# GSMGPSMC60_2.net
KiCad netlist of a schematic drawn in Altium Designer
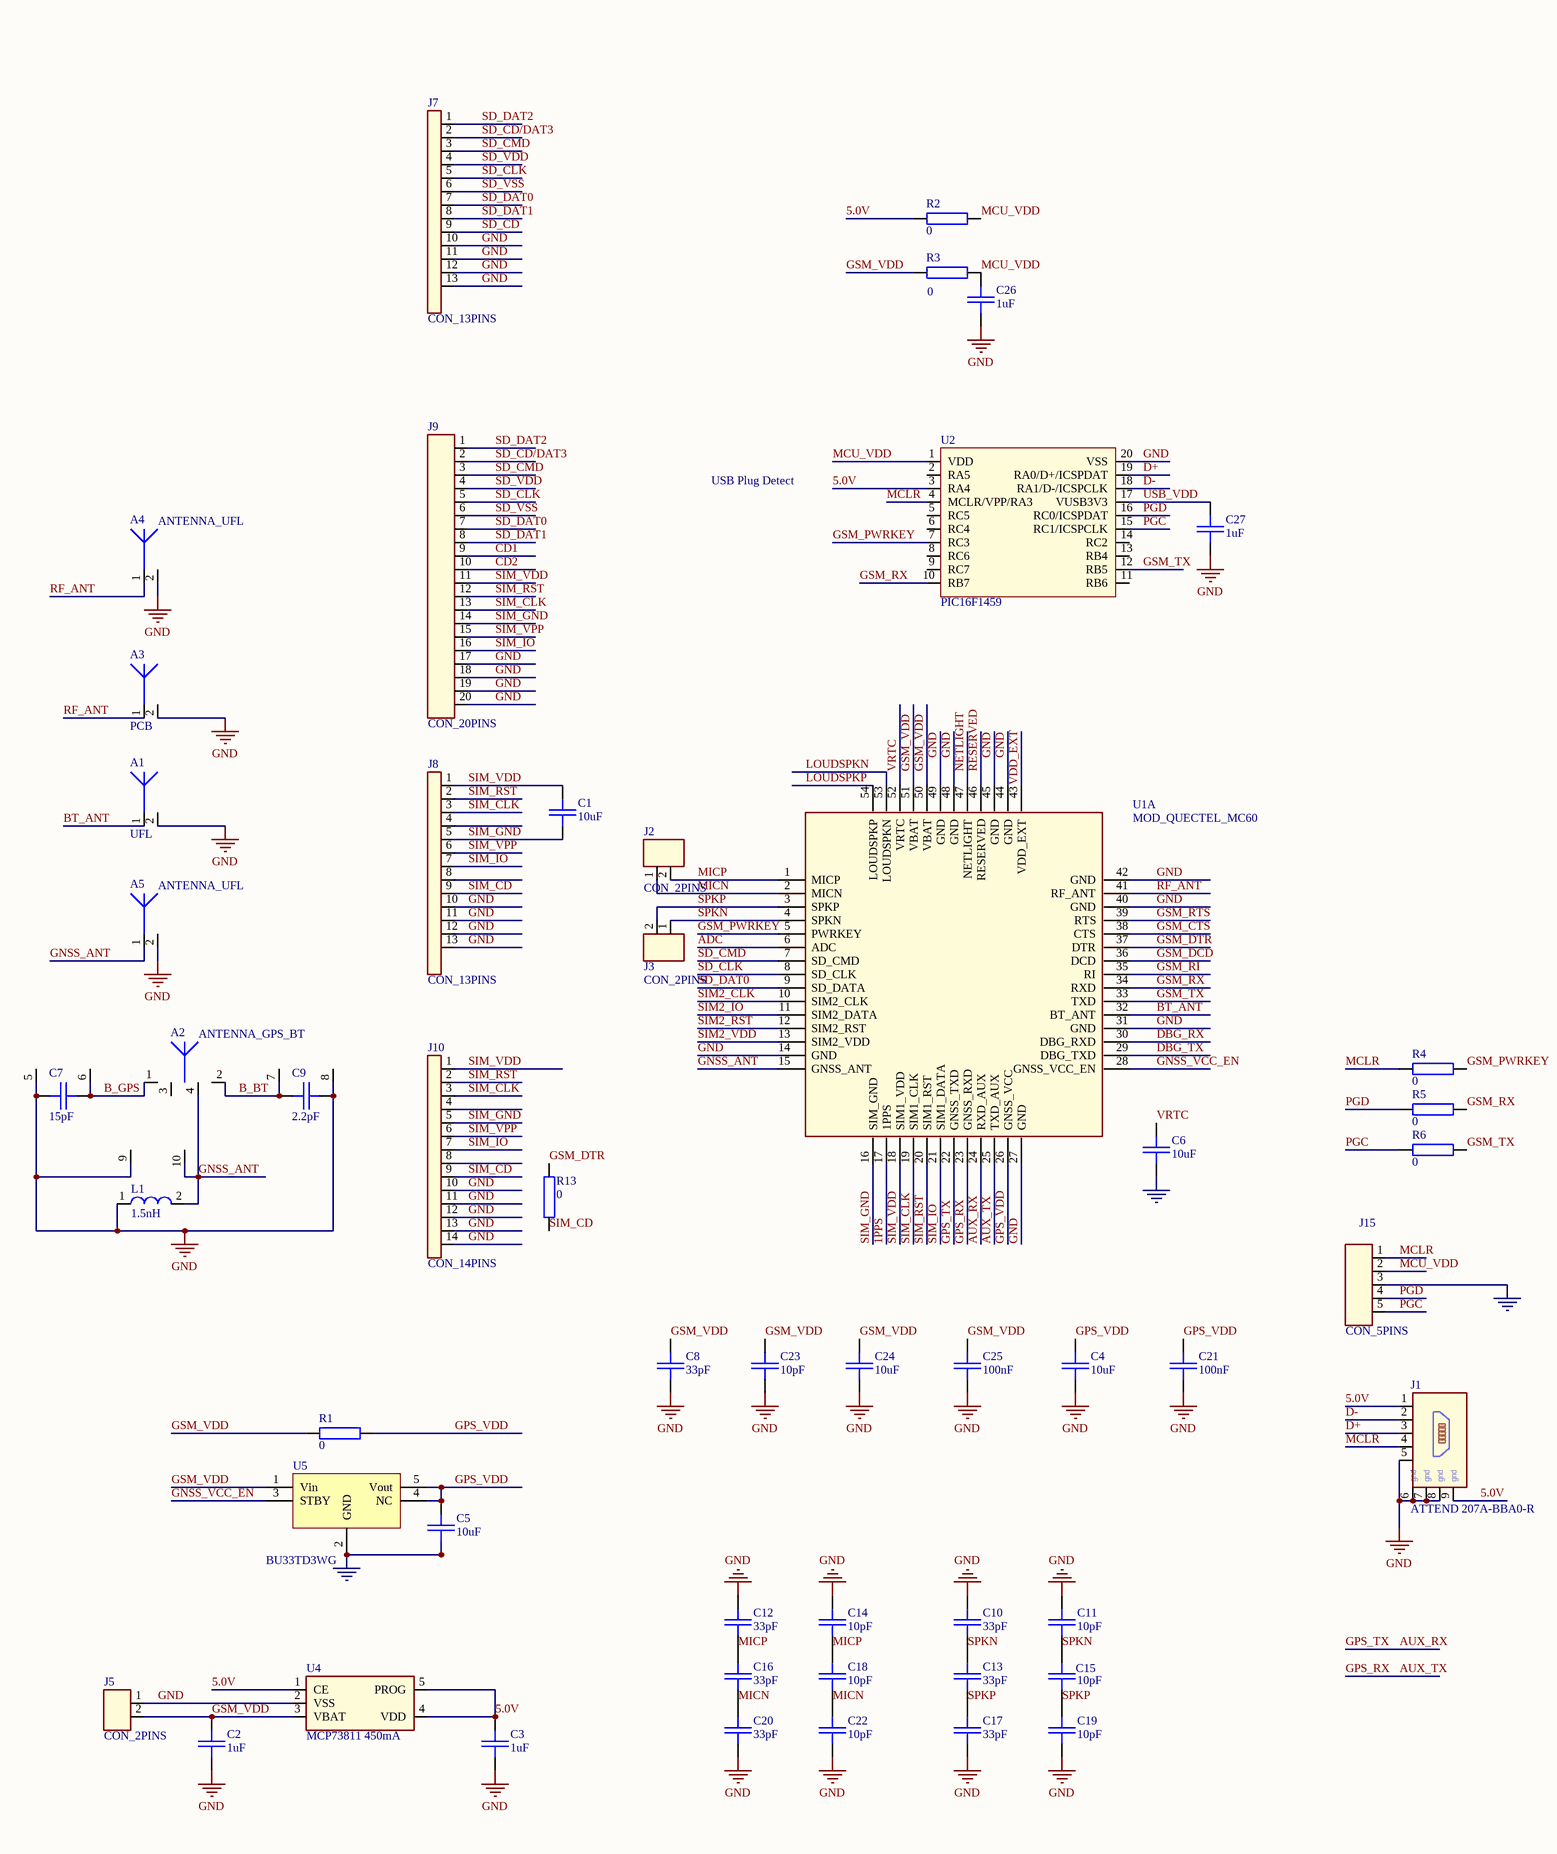
[diagram p0: GSMGPSMC60_2.SchDoc, left]
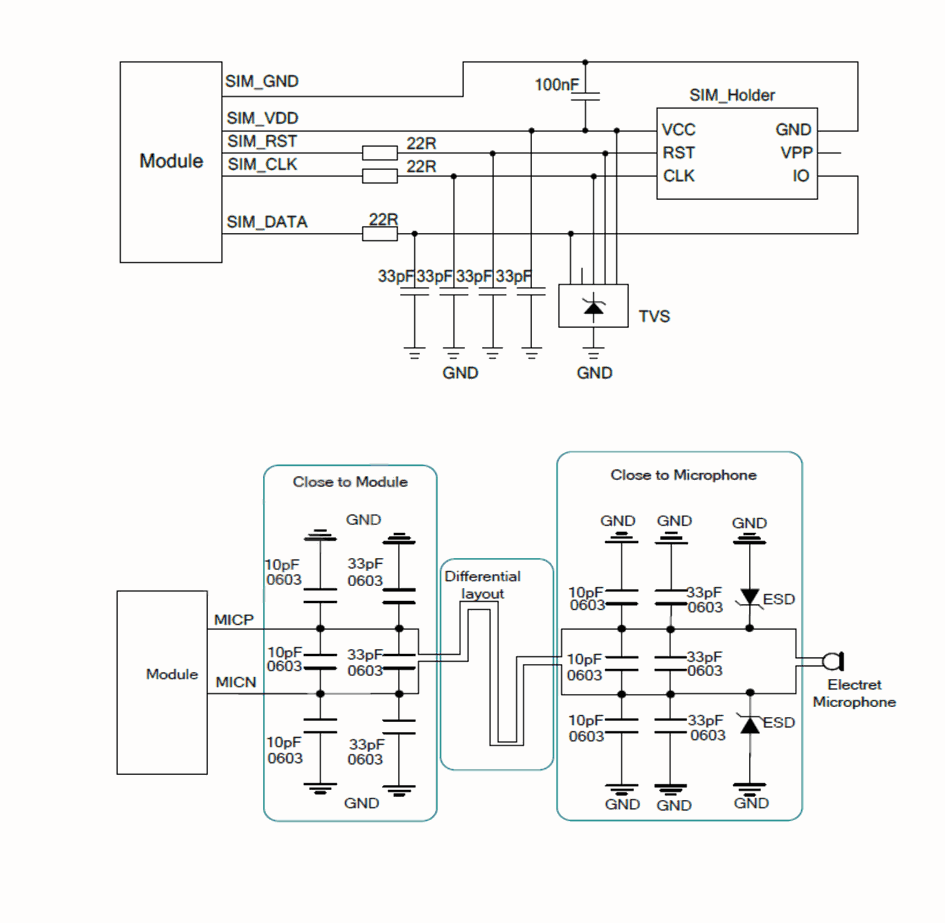
[diagram p1: GSMGPSMC60_2.SchDoc, right]

(export (version "E")
  (design (tool "Eeschema 10.0.6"))
  (components
    (comp (ref "A1")
      (value "UFL")
      (footprint "SMD_CON_ANTENNA_UFL")
      (libsource (lib "DLV") (part "ANTENNA_2"))
    )
    (comp (ref "A2")
      (value "ANTENNA_GPS_BT")
      (footprint "SMD_CHIP_ANTENNA_GPS_BT - FLIP")
      (libsource (lib "DLV") (part "ANTENNA_GPS_BT"))
    )
    (comp (ref "A3")
      (value "PCB")
      (footprint "SMD_CON_ANTENNA_GSM_PCB")
      (libsource (lib "DLV") (part "ANTENNA_2"))
    )
    (comp (ref "A4")
      (value "ANTENNA_UFL")
      (footprint "SMD_CON_ANTENNA_UFL")
      (libsource (lib "DLV") (part "ANTENNA_2"))
    )
    (comp (ref "A5")
      (value "ANTENNA_UFL")
      (footprint "SMD_CON_ANTENNA_UFL")
      (libsource (lib "DLV") (part "ANTENNA_2"))
    )
    (comp (ref "C1") (value "10uF") (footprint "SMD_0402_CAPC1005X90N") (libsource (lib "DLV") (part "C")))
    (comp (ref "C2") (value "1uF") (footprint "SMD_0402_CAPC1005X90N") (libsource (lib "DLV") (part "C")))
    (comp (ref "C3") (value "1uF") (footprint "SMD_0402_CAPC1005X90N") (libsource (lib "DLV") (part "C")))
    (comp (ref "C4") (value "10uF") (footprint "SMD_0402_CAPC1005X90N") (libsource (lib "DLV") (part "C")))
    (comp (ref "C5") (value "10uF") (footprint "SMD_0402_CAPC1005X90N") (libsource (lib "DLV") (part "C")))
    (comp (ref "C6") (value "10uF") (footprint "SMD_0402_CAPC1005X90N") (libsource (lib "DLV") (part "C")))
    (comp (ref "C7")
      (value "15pF")
      (footprint "SMD_0402_CAPC1005X90N - ANTENNA")
      (libsource (lib "DLV") (part "C"))
    )
    (comp (ref "C8") (value "33pF") (footprint "SMD_0402_CAPC1005X90N") (libsource (lib "DLV") (part "C")))
    (comp (ref "C9")
      (value "2.2pF")
      (footprint "SMD_0201_CAPC0603X33N - ANTENNA")
      (libsource (lib "DLV") (part "C"))
    )
    (comp (ref "C10") (value "33pF") (footprint "SMD_0402_CAPC1005X90N") (libsource (lib "DLV") (part "C")))
    (comp (ref "C11") (value "10pF") (footprint "SMD_0402_CAPC1005X90N") (libsource (lib "DLV") (part "C")))
    (comp (ref "C12") (value "33pF") (footprint "SMD_0402_CAPC1005X90N") (libsource (lib "DLV") (part "C")))
    (comp (ref "C13") (value "33pF") (footprint "SMD_0402_CAPC1005X90N") (libsource (lib "DLV") (part "C")))
    (comp (ref "C14") (value "10pF") (footprint "SMD_0402_CAPC1005X90N") (libsource (lib "DLV") (part "C")))
    (comp (ref "C15") (value "10pF") (footprint "SMD_0402_CAPC1005X90N") (libsource (lib "DLV") (part "C")))
    (comp (ref "C16") (value "33pF") (footprint "SMD_0402_CAPC1005X90N") (libsource (lib "DLV") (part "C")))
    (comp (ref "C17") (value "33pF") (footprint "SMD_0402_CAPC1005X90N") (libsource (lib "DLV") (part "C")))
    (comp (ref "C18") (value "10pF") (footprint "SMD_0402_CAPC1005X90N") (libsource (lib "DLV") (part "C")))
    (comp (ref "C19") (value "10pF") (footprint "SMD_0402_CAPC1005X90N") (libsource (lib "DLV") (part "C")))
    (comp (ref "C20") (value "33pF") (footprint "SMD_0402_CAPC1005X90N") (libsource (lib "DLV") (part "C")))
    (comp (ref "C21") (value "100nF") (footprint "SMD_0402_CAPC1005X90N") (libsource (lib "DLV") (part "C")))
    (comp (ref "C22") (value "10pF") (footprint "SMD_0402_CAPC1005X90N") (libsource (lib "DLV") (part "C")))
    (comp (ref "C23") (value "10pF") (footprint "SMD_0402_CAPC1005X90N") (libsource (lib "DLV") (part "C")))
    (comp (ref "C24") (value "10uF") (footprint "SMD_0402_CAPC1005X90N") (libsource (lib "DLV") (part "C")))
    (comp (ref "C25") (value "100nF") (footprint "SMD_0402_CAPC1005X90N") (libsource (lib "DLV") (part "C")))
    (comp (ref "C26") (value "1uF") (footprint "SMD_0402_CAPC1005X90N") (libsource (lib "DLV") (part "C")))
    (comp (ref "C27") (value "1uF") (footprint "SMD_0402_CAPC1005X90N") (libsource (lib "DLV") (part "C")))
    (comp (ref "J1")
      (value "ATTEND 207A-BBA0-R")
      (footprint "SMD_CON_MICRO_USB")
      (libsource (lib "DLV") (part "CON_USB_MINI"))
    )
    (comp (ref "J2")
      (value "CON_2PINS")
      (footprint "PTH_MIC_6MM_2.7MM_PITCH1.9")
      (libsource (lib "") (part "CON_2PINS_1"))
    )
    (comp (ref "J3")
      (value "CON_2PINS")
      (footprint "PTH_MIC_6MM_2.7MM_PITCH1.9")
      (libsource (lib "DLV") (part "CON_2PINS"))
    )
    (comp (ref "J5")
      (value "CON_2PINS")
      (footprint "PTH_HDRV02W64P254_1X02")
      (libsource (lib "DLV") (part "CON_2PINS"))
    )
    (comp (ref "J7") (value "CON_13PINS") (footprint "NONE") (libsource (lib "DLV") (part "CON_13PINS")))
    (comp (ref "J8")
      (value "CON_13PINS")
      (footprint "SMD_CON-ATTEND_MICRO_SIM_115Q-BCA0")
      (libsource (lib "DLV") (part "CON_13PINS"))
    )
    (comp (ref "J9") (value "CON_20PINS") (footprint "NONE") (libsource (lib "DLV") (part "CON_20PINS")))
    (comp (ref "J10") (value "CON_14PINS") (footprint "NONE") (libsource (lib "DLV") (part "CON_14PINS")))
    (comp (ref "J15") (value "CON_5PINS") (footprint "SIP5 - PGM") (libsource (lib "DLV") (part "CON_5PINS")))
    (comp (ref "L1")
      (value "1.5nH")
      (footprint "SMD_0402_INDC1005X55N - ANTENNA")
      (libsource (lib "DLV") (part "L"))
    )
    (comp (ref "R1") (value "0") (footprint "SMD_0402_RESC1005X37N") (libsource (lib "DLV") (part "R")))
    (comp (ref "R2") (value "0") (footprint "SMD_0402_RESC1005X37N") (libsource (lib "DLV") (part "R")))
    (comp (ref "R3") (value "0") (footprint "SMD_0402_RESC1005X37N") (libsource (lib "DLV") (part "R")))
    (comp (ref "R4") (value "0") (footprint "SMD_0402_RESC1005X37N") (libsource (lib "DLV") (part "R")))
    (comp (ref "R5") (value "0") (footprint "SMD_0402_RESC1005X37N") (libsource (lib "DLV") (part "R")))
    (comp (ref "R6") (value "0") (footprint "SMD_0402_RESC1005X37N") (libsource (lib "DLV") (part "R")))
    (comp (ref "R13") (value "0") (footprint "SMD_0402_RESC1005X37N") (libsource (lib "DLV") (part "R")))
    (comp (ref "U1")
      (value "MOD_QUECTEL_MC60")
      (footprint "SMD_MOD_MC60_54_PIN")
      (libsource (lib "DLV") (part "MOD_QUECTEL_MC60"))
    )
    (comp (ref "U2")
      (value "PIC16F1459")
      (footprint "SMD_QFN50P400X400X90-21N")
      (libsource (lib "DLV") (part "IC_PIC16F1459"))
    )
    (comp (ref "U4")
      (value "MCP73811 450mA")
      (footprint "SMD_SOT26_SOT95P285X140-5N - DLV")
      (description "MCP73812")
      (fields
        (field (name "DB_PART_NUMBER") "PSU000000127")
        (field (name "DB_MANUFACTURER_PART") "ROHM        BD33KA5WF-E2")
        (field (name "DB_APPROVED_BY") "VSN")
      )
      (libsource (lib "DLV") (part "IC_MCP73812"))
    )
    (comp (ref "U5")
      (value "BU33TD3WG")
      (footprint "SMD_SOT26_SOT95P285X140-5N - DLV")
      (libsource (lib "DLV") (part "IC_BU33TD3WG"))
    )
  )
  (nets
    (net (code "1") (name "/1PPS") (class "Default")
      (node (ref "U1") (pin "17") (pinfunction "1PPS_17") (pintype "passive"))
    )
    (net (code "2") (name "/5.0V") (class "Default")
      (node (ref "C3") (pin "1") (pinfunction "1_1") (pintype "passive"))
      (node (ref "J1") (pin "1") (pinfunction "1_1") (pintype "passive"))
      (node (ref "J1") (pin "9") (pinfunction "9_9") (pintype "passive"))
      (node (ref "R2") (pin "1") (pinfunction "1_1") (pintype "passive"))
      (node (ref "U2") (pin "3") (pinfunction "RA4_3") (pintype "passive"))
      (node (ref "U4") (pin "1") (pinfunction "CE_1") (pintype "passive"))
      (node (ref "U4") (pin "4") (pinfunction "VDD_4") (pintype "passive"))
      (node (ref "U4") (pin "5") (pinfunction "PROG_5") (pintype "passive"))
    )
    (net (code "3") (name "/ADC") (class "Default")
      (node (ref "U1") (pin "6") (pinfunction "ADC_6") (pintype "passive"))
    )
    (net (code "4") (name "/AUX_RX") (class "Default")
      (node (ref "U1") (pin "22") (pinfunction "GNSS_TXD_22") (pintype "passive"))
      (node (ref "U1") (pin "24") (pinfunction "RXD_AUX_24") (pintype "passive"))
    )
    (net (code "5") (name "/AUX_TX") (class "Default")
      (node (ref "U1") (pin "23") (pinfunction "GNSS_RXD_23") (pintype "passive"))
      (node (ref "U1") (pin "25") (pinfunction "TXD_AUX_25") (pintype "passive"))
    )
    (net (code "6") (name "/BT_ANT") (class "Default")
      (node (ref "A1") (pin "1") (pinfunction "1_1") (pintype "passive"))
      (node (ref "U1") (pin "32") (pinfunction "BT_ANT_32") (pintype "passive"))
    )
    (net (code "7") (name "/B_BT") (class "Default")
      (node (ref "A2") (pin "2") (pinfunction "2_2") (pintype "passive"))
      (node (ref "A2") (pin "7") (pinfunction "7_7") (pintype "passive"))
      (node (ref "C9") (pin "1") (pinfunction "1_1") (pintype "passive"))
    )
    (net (code "8") (name "/B_GPS") (class "Default")
      (node (ref "A2") (pin "1") (pinfunction "1_1") (pintype "passive"))
      (node (ref "A2") (pin "6") (pinfunction "6_6") (pintype "passive"))
      (node (ref "C7") (pin "2") (pinfunction "2_2") (pintype "passive"))
    )
    (net (code "9") (name "/CD1") (class "Default")
      (node (ref "J9") (pin "9") (pinfunction "9_9") (pintype "passive"))
    )
    (net (code "10") (name "/CD2") (class "Default")
      (node (ref "J9") (pin "10") (pinfunction "10_10") (pintype "passive"))
    )
    (net (code "11") (name "/D+") (class "Default")
      (node (ref "J1") (pin "3") (pinfunction "3_3") (pintype "passive"))
      (node (ref "U2") (pin "19") (pinfunction "RA0/D+/ICSPDAT_19") (pintype "passive"))
    )
    (net (code "12") (name "/D-") (class "Default")
      (node (ref "J1") (pin "2") (pinfunction "2_2") (pintype "passive"))
      (node (ref "U2") (pin "18") (pinfunction "RA1/D-/ICSPCLK_18") (pintype "passive"))
    )
    (net (code "13") (name "/DBG_RX") (class "Default")
      (node (ref "U1") (pin "30") (pinfunction "DBG_RXD_30") (pintype "passive"))
    )
    (net (code "14") (name "/DBG_TX") (class "Default")
      (node (ref "U1") (pin "29") (pinfunction "DBG_TXD_29") (pintype "passive"))
    )
    (net (code "15") (name "/GNSS_ANT") (class "Default")
      (node (ref "A2") (pin "10") (pinfunction "10_10") (pintype "passive"))
      (node (ref "A2") (pin "4") (pinfunction "4_4") (pintype "passive"))
      (node (ref "A5") (pin "1") (pinfunction "1_1") (pintype "passive"))
      (node (ref "L1") (pin "2") (pinfunction "2_2") (pintype "passive"))
      (node (ref "U1") (pin "15") (pinfunction "GNSS_ANT_15") (pintype "passive"))
    )
    (net (code "16") (name "/GNSS_VCC_EN") (class "Default")
      (node (ref "U1") (pin "28") (pinfunction "GNSS_VCC_EN_28") (pintype "passive"))
      (node (ref "U5") (pin "3") (pinfunction "STBY_3") (pintype "passive"))
    )
    (net (code "17") (name "/GPS_VDD") (class "Default")
      (node (ref "C21") (pin "1") (pinfunction "1_1") (pintype "passive"))
      (node (ref "C4") (pin "1") (pinfunction "1_1") (pintype "passive"))
      (node (ref "C5") (pin "1") (pinfunction "1_1") (pintype "passive"))
      (node (ref "R1") (pin "2") (pinfunction "2_2") (pintype "passive"))
      (node (ref "U1") (pin "26") (pinfunction "GNSS_VCC_26") (pintype "passive"))
      (node (ref "U5") (pin "4") (pinfunction "NC_4") (pintype "passive"))
      (node (ref "U5") (pin "5") (pinfunction "Vout_5") (pintype "passive"))
    )
    (net (code "18") (name "/GSM_CTS") (class "Default")
      (node (ref "U1") (pin "38") (pinfunction "CTS_38") (pintype "passive"))
    )
    (net (code "19") (name "/GSM_DCD") (class "Default")
      (node (ref "U1") (pin "36") (pinfunction "DCD_36") (pintype "passive"))
    )
    (net (code "20") (name "/GSM_DTR") (class "Default")
      (node (ref "R13") (pin "1") (pinfunction "1_1") (pintype "passive"))
      (node (ref "U1") (pin "37") (pinfunction "DTR_37") (pintype "passive"))
    )
    (net (code "21") (name "/GSM_PWRKEY") (class "Default")
      (node (ref "R4") (pin "2") (pinfunction "2_2") (pintype "passive"))
      (node (ref "U1") (pin "5") (pinfunction "PWRKEY_5") (pintype "passive"))
      (node (ref "U2") (pin "7") (pinfunction "RC3_7") (pintype "passive"))
    )
    (net (code "22") (name "/GSM_RI") (class "Default")
      (node (ref "U1") (pin "35") (pinfunction "RI_35") (pintype "passive"))
    )
    (net (code "23") (name "/GSM_RTS") (class "Default")
      (node (ref "U1") (pin "39") (pinfunction "RTS_39") (pintype "passive"))
    )
    (net (code "24") (name "/GSM_RX") (class "Default")
      (node (ref "R5") (pin "2") (pinfunction "2_2") (pintype "passive"))
      (node (ref "U1") (pin "34") (pinfunction "RXD_34") (pintype "passive"))
      (node (ref "U2") (pin "10") (pinfunction "RB7_10") (pintype "passive"))
    )
    (net (code "25") (name "/GSM_TX") (class "Default")
      (node (ref "R6") (pin "2") (pinfunction "2_2") (pintype "passive"))
      (node (ref "U1") (pin "33") (pinfunction "TXD_33") (pintype "passive"))
      (node (ref "U2") (pin "12") (pinfunction "RB5_12") (pintype "passive"))
    )
    (net (code "26") (name "/GSM_VDD") (class "Default")
      (node (ref "C2") (pin "1") (pinfunction "1_1") (pintype "passive"))
      (node (ref "C23") (pin "1") (pinfunction "1_1") (pintype "passive"))
      (node (ref "C24") (pin "1") (pinfunction "1_1") (pintype "passive"))
      (node (ref "C25") (pin "1") (pinfunction "1_1") (pintype "passive"))
      (node (ref "C8") (pin "1") (pinfunction "1_1") (pintype "passive"))
      (node (ref "J5") (pin "2") (pinfunction "2_2") (pintype "passive"))
      (node (ref "R1") (pin "1") (pinfunction "1_1") (pintype "passive"))
      (node (ref "R3") (pin "1") (pinfunction "1_1") (pintype "passive"))
      (node (ref "U1") (pin "50") (pinfunction "VBAT_50") (pintype "passive"))
      (node (ref "U1") (pin "51") (pinfunction "VBAT_51") (pintype "passive"))
      (node (ref "U4") (pin "3") (pinfunction "VBAT_3") (pintype "passive"))
      (node (ref "U5") (pin "1") (pinfunction "Vin_1") (pintype "passive"))
    )
    (net (code "27") (name "/LOUDSPKN") (class "Default")
      (node (ref "U1") (pin "53") (pinfunction "LOUDSPKN_53") (pintype "passive"))
    )
    (net (code "28") (name "/LOUDSPKP") (class "Default")
      (node (ref "U1") (pin "54") (pinfunction "LOUDSPKP_54") (pintype "passive"))
    )
    (net (code "29") (name "/MCLR") (class "Default")
      (node (ref "J1") (pin "4") (pinfunction "4_4") (pintype "passive"))
      (node (ref "J15") (pin "1") (pinfunction "1_1") (pintype "passive"))
      (node (ref "R4") (pin "1") (pinfunction "1_1") (pintype "passive"))
      (node (ref "U2") (pin "4") (pinfunction "MCLR/VPP/RA3_4") (pintype "passive"))
    )
    (net (code "30") (name "/MCU_VDD") (class "Default")
      (node (ref "C26") (pin "1") (pinfunction "1_1") (pintype "passive"))
      (node (ref "J15") (pin "2") (pinfunction "2_2") (pintype "passive"))
      (node (ref "R2") (pin "2") (pinfunction "2_2") (pintype "passive"))
      (node (ref "R3") (pin "2") (pinfunction "2_2") (pintype "passive"))
      (node (ref "U2") (pin "1") (pinfunction "VDD_1") (pintype "passive"))
    )
    (net (code "31") (name "/MICN") (class "Default")
      (node (ref "C16") (pin "2") (pinfunction "2_2") (pintype "passive"))
      (node (ref "C18") (pin "2") (pinfunction "2_2") (pintype "passive"))
      (node (ref "C20") (pin "1") (pinfunction "1_1") (pintype "passive"))
      (node (ref "C22") (pin "1") (pinfunction "1_1") (pintype "passive"))
      (node (ref "J2") (pin "1") (pinfunction "1_1") (pintype "passive"))
      (node (ref "U1") (pin "2") (pinfunction "MICN_2") (pintype "passive"))
    )
    (net (code "32") (name "/MICP") (class "Default")
      (node (ref "C12") (pin "2") (pinfunction "2_2") (pintype "passive"))
      (node (ref "C14") (pin "2") (pinfunction "2_2") (pintype "passive"))
      (node (ref "C16") (pin "1") (pinfunction "1_1") (pintype "passive"))
      (node (ref "C18") (pin "1") (pinfunction "1_1") (pintype "passive"))
      (node (ref "J2") (pin "2") (pinfunction "2_2") (pintype "passive"))
      (node (ref "U1") (pin "1") (pinfunction "MICP_1") (pintype "passive"))
    )
    (net (code "33") (name "/NETLIGHT") (class "Default")
      (node (ref "U1") (pin "47") (pinfunction "NETLIGHT_47") (pintype "passive"))
    )
    (net (code "34") (name "/PGC") (class "Default")
      (node (ref "J15") (pin "5") (pinfunction "5_5") (pintype "passive"))
      (node (ref "R6") (pin "1") (pinfunction "1_1") (pintype "passive"))
      (node (ref "U2") (pin "15") (pinfunction "RC1/ICSPCLK_15") (pintype "passive"))
    )
    (net (code "35") (name "/PGD") (class "Default")
      (node (ref "J15") (pin "4") (pinfunction "4_4") (pintype "passive"))
      (node (ref "R5") (pin "1") (pinfunction "1_1") (pintype "passive"))
      (node (ref "U2") (pin "16") (pinfunction "RC0/ICSPDAT_16") (pintype "passive"))
    )
    (net (code "36") (name "/RESERVED") (class "Default")
      (node (ref "U1") (pin "46") (pinfunction "RESERVED_46") (pintype "passive"))
    )
    (net (code "37") (name "/RF_ANT") (class "Default")
      (node (ref "A3") (pin "1") (pinfunction "1_1") (pintype "passive"))
      (node (ref "A4") (pin "1") (pinfunction "1_1") (pintype "passive"))
      (node (ref "U1") (pin "41") (pinfunction "RF_ANT_41") (pintype "passive"))
    )
    (net (code "38") (name "/SD_CD") (class "Default")
      (node (ref "J7") (pin "9") (pinfunction "9_9") (pintype "passive"))
    )
    (net (code "39") (name "/SD_CD{slash}DAT3") (class "Default")
      (node (ref "J7") (pin "2") (pinfunction "2_2") (pintype "passive"))
      (node (ref "J9") (pin "2") (pinfunction "2_2") (pintype "passive"))
    )
    (net (code "40") (name "/SD_CLK") (class "Default")
      (node (ref "J7") (pin "5") (pinfunction "5_5") (pintype "passive"))
      (node (ref "J9") (pin "5") (pinfunction "5_5") (pintype "passive"))
      (node (ref "U1") (pin "8") (pinfunction "SD_CLK_8") (pintype "passive"))
    )
    (net (code "41") (name "/SD_CMD") (class "Default")
      (node (ref "J7") (pin "3") (pinfunction "3_3") (pintype "passive"))
      (node (ref "J9") (pin "3") (pinfunction "3_3") (pintype "passive"))
      (node (ref "U1") (pin "7") (pinfunction "SD_CMD_7") (pintype "passive"))
    )
    (net (code "42") (name "/SD_DAT0") (class "Default")
      (node (ref "J7") (pin "7") (pinfunction "7_7") (pintype "passive"))
      (node (ref "J9") (pin "7") (pinfunction "7_7") (pintype "passive"))
      (node (ref "U1") (pin "9") (pinfunction "SD_DATA_9") (pintype "passive"))
    )
    (net (code "43") (name "/SD_DAT1") (class "Default")
      (node (ref "J7") (pin "8") (pinfunction "8_8") (pintype "passive"))
      (node (ref "J9") (pin "8") (pinfunction "8_8") (pintype "passive"))
    )
    (net (code "44") (name "/SD_DAT2") (class "Default")
      (node (ref "J7") (pin "1") (pinfunction "1_1") (pintype "passive"))
      (node (ref "J9") (pin "1") (pinfunction "1_1") (pintype "passive"))
    )
    (net (code "45") (name "/SD_VDD") (class "Default")
      (node (ref "J7") (pin "4") (pinfunction "4_4") (pintype "passive"))
      (node (ref "J9") (pin "4") (pinfunction "4_4") (pintype "passive"))
    )
    (net (code "46") (name "/SD_VSS") (class "Default")
      (node (ref "J7") (pin "6") (pinfunction "6_6") (pintype "passive"))
      (node (ref "J9") (pin "6") (pinfunction "6_6") (pintype "passive"))
    )
    (net (code "47") (name "/SIM2_CLK") (class "Default")
      (node (ref "U1") (pin "10") (pinfunction "SIM2_CLK_10") (pintype "passive"))
    )
    (net (code "48") (name "/SIM2_IO") (class "Default")
      (node (ref "U1") (pin "11") (pinfunction "SIM2_DATA_11") (pintype "passive"))
    )
    (net (code "49") (name "/SIM2_RST") (class "Default")
      (node (ref "U1") (pin "12") (pinfunction "SIM2_RST_12") (pintype "passive"))
    )
    (net (code "50") (name "/SIM2_VDD") (class "Default")
      (node (ref "U1") (pin "13") (pinfunction "SIM2_VDD_13") (pintype "passive"))
    )
    (net (code "51") (name "/SIM_CD") (class "Default")
      (node (ref "J10") (pin "9") (pinfunction "9_9") (pintype "passive"))
      (node (ref "J8") (pin "9") (pinfunction "9_9") (pintype "passive"))
      (node (ref "R13") (pin "2") (pinfunction "2_2") (pintype "passive"))
    )
    (net (code "52") (name "/SIM_CLK") (class "Default")
      (node (ref "J10") (pin "3") (pinfunction "3_3") (pintype "passive"))
      (node (ref "J8") (pin "3") (pinfunction "3_3") (pintype "passive"))
      (node (ref "J9") (pin "13") (pinfunction "13_13") (pintype "passive"))
      (node (ref "U1") (pin "19") (pinfunction "SIM1_CLK_19") (pintype "passive"))
    )
    (net (code "53") (name "/SIM_GND") (class "Default")
      (node (ref "C1") (pin "2") (pinfunction "2_2") (pintype "passive"))
      (node (ref "J10") (pin "5") (pinfunction "5_5") (pintype "passive"))
      (node (ref "J8") (pin "5") (pinfunction "5_5") (pintype "passive"))
      (node (ref "J9") (pin "14") (pinfunction "14_14") (pintype "passive"))
      (node (ref "U1") (pin "16") (pinfunction "SIM_GND_16") (pintype "passive"))
    )
    (net (code "54") (name "/SIM_IO") (class "Default")
      (node (ref "J10") (pin "7") (pinfunction "7_7") (pintype "passive"))
      (node (ref "J8") (pin "7") (pinfunction "7_7") (pintype "passive"))
      (node (ref "J9") (pin "16") (pinfunction "16_16") (pintype "passive"))
      (node (ref "U1") (pin "21") (pinfunction "SIM1_DATA_21") (pintype "passive"))
    )
    (net (code "55") (name "/SIM_RST") (class "Default")
      (node (ref "J10") (pin "2") (pinfunction "2_2") (pintype "passive"))
      (node (ref "J8") (pin "2") (pinfunction "2_2") (pintype "passive"))
      (node (ref "J9") (pin "12") (pinfunction "12_12") (pintype "passive"))
      (node (ref "U1") (pin "20") (pinfunction "SIM1_RST_20") (pintype "passive"))
    )
    (net (code "56") (name "/SIM_VDD") (class "Default")
      (node (ref "C1") (pin "1") (pinfunction "1_1") (pintype "passive"))
      (node (ref "J10") (pin "1") (pinfunction "1_1") (pintype "passive"))
      (node (ref "J8") (pin "1") (pinfunction "1_1") (pintype "passive"))
      (node (ref "J9") (pin "11") (pinfunction "11_11") (pintype "passive"))
      (node (ref "U1") (pin "18") (pinfunction "SIM1_VDD_18") (pintype "passive"))
    )
    (net (code "57") (name "/SIM_VPP") (class "Default")
      (node (ref "J10") (pin "6") (pinfunction "6_6") (pintype "passive"))
      (node (ref "J8") (pin "6") (pinfunction "6_6") (pintype "passive"))
      (node (ref "J9") (pin "15") (pinfunction "15_15") (pintype "passive"))
    )
    (net (code "58") (name "/SPKN") (class "Default")
      (node (ref "C10") (pin "2") (pinfunction "2_2") (pintype "passive"))
      (node (ref "C11") (pin "2") (pinfunction "2_2") (pintype "passive"))
      (node (ref "C13") (pin "1") (pinfunction "1_1") (pintype "passive"))
      (node (ref "C15") (pin "1") (pinfunction "1_1") (pintype "passive"))
      (node (ref "J3") (pin "1") (pinfunction "1_1") (pintype "passive"))
      (node (ref "U1") (pin "4") (pinfunction "SPKN_4") (pintype "passive"))
    )
    (net (code "59") (name "/SPKP") (class "Default")
      (node (ref "C13") (pin "2") (pinfunction "2_2") (pintype "passive"))
      (node (ref "C15") (pin "2") (pinfunction "2_2") (pintype "passive"))
      (node (ref "C17") (pin "1") (pinfunction "1_1") (pintype "passive"))
      (node (ref "C19") (pin "1") (pinfunction "1_1") (pintype "passive"))
      (node (ref "J3") (pin "2") (pinfunction "2_2") (pintype "passive"))
      (node (ref "U1") (pin "3") (pinfunction "SPKP_3") (pintype "passive"))
    )
    (net (code "60") (name "/USB_VDD") (class "Default")
      (node (ref "C27") (pin "1") (pinfunction "1_1") (pintype "passive"))
      (node (ref "U2") (pin "17") (pinfunction "VUSB3V3_17") (pintype "passive"))
    )
    (net (code "61") (name "/VDD_EXT") (class "Default")
      (node (ref "U1") (pin "43") (pinfunction "VDD_EXT_43") (pintype "passive"))
    )
    (net (code "62") (name "/VRTC") (class "Default")
      (node (ref "C6") (pin "1") (pinfunction "1_1") (pintype "passive"))
      (node (ref "U1") (pin "52") (pinfunction "VRTC_52") (pintype "passive"))
    )
    (net (code "63") (name "GND") (class "Default")
      (node (ref "A1") (pin "2") (pinfunction "2_2") (pintype "passive"))
      (node (ref "A2") (pin "5") (pinfunction "5_5") (pintype "passive"))
      (node (ref "A2") (pin "8") (pinfunction "8_8") (pintype "passive"))
      (node (ref "A2") (pin "9") (pinfunction "9_9") (pintype "passive"))
      (node (ref "A3") (pin "2") (pinfunction "2_2") (pintype "passive"))
      (node (ref "A4") (pin "2") (pinfunction "2_2") (pintype "passive"))
      (node (ref "A5") (pin "2") (pinfunction "2_2") (pintype "passive"))
      (node (ref "C10") (pin "1") (pinfunction "1_1") (pintype "passive"))
      (node (ref "C11") (pin "1") (pinfunction "1_1") (pintype "passive"))
      (node (ref "C12") (pin "1") (pinfunction "1_1") (pintype "passive"))
      (node (ref "C14") (pin "1") (pinfunction "1_1") (pintype "passive"))
      (node (ref "C17") (pin "2") (pinfunction "2_2") (pintype "passive"))
      (node (ref "C19") (pin "2") (pinfunction "2_2") (pintype "passive"))
      (node (ref "C2") (pin "2") (pinfunction "2_2") (pintype "passive"))
      (node (ref "C20") (pin "2") (pinfunction "2_2") (pintype "passive"))
      (node (ref "C21") (pin "2") (pinfunction "2_2") (pintype "passive"))
      (node (ref "C22") (pin "2") (pinfunction "2_2") (pintype "passive"))
      (node (ref "C23") (pin "2") (pinfunction "2_2") (pintype "passive"))
      (node (ref "C24") (pin "2") (pinfunction "2_2") (pintype "passive"))
      (node (ref "C25") (pin "2") (pinfunction "2_2") (pintype "passive"))
      (node (ref "C26") (pin "2") (pinfunction "2_2") (pintype "passive"))
      (node (ref "C27") (pin "2") (pinfunction "2_2") (pintype "passive"))
      (node (ref "C3") (pin "2") (pinfunction "2_2") (pintype "passive"))
      (node (ref "C4") (pin "2") (pinfunction "2_2") (pintype "passive"))
      (node (ref "C5") (pin "2") (pinfunction "2_2") (pintype "passive"))
      (node (ref "C6") (pin "2") (pinfunction "2_2") (pintype "passive"))
      (node (ref "C7") (pin "1") (pinfunction "1_1") (pintype "passive"))
      (node (ref "C8") (pin "2") (pinfunction "2_2") (pintype "passive"))
      (node (ref "C9") (pin "2") (pinfunction "2_2") (pintype "passive"))
      (node (ref "J1") (pin "5") (pinfunction "5_5") (pintype "passive"))
      (node (ref "J1") (pin "6") (pinfunction "6_6") (pintype "passive"))
      (node (ref "J1") (pin "7") (pinfunction "7_7") (pintype "passive"))
      (node (ref "J1") (pin "8") (pinfunction "8_8") (pintype "passive"))
      (node (ref "J10") (pin "10") (pinfunction "10_10") (pintype "passive"))
      (node (ref "J10") (pin "11") (pinfunction "11_11") (pintype "passive"))
      (node (ref "J10") (pin "12") (pinfunction "12_12") (pintype "passive"))
      (node (ref "J10") (pin "13") (pinfunction "13_13") (pintype "passive"))
      (node (ref "J10") (pin "14") (pinfunction "14_14") (pintype "passive"))
      (node (ref "J15") (pin "3") (pinfunction "3_3") (pintype "passive"))
      (node (ref "J5") (pin "1") (pinfunction "1_1") (pintype "passive"))
      (node (ref "J7") (pin "10") (pinfunction "10_10") (pintype "passive"))
      (node (ref "J7") (pin "11") (pinfunction "11_11") (pintype "passive"))
      (node (ref "J7") (pin "12") (pinfunction "12_12") (pintype "passive"))
      (node (ref "J7") (pin "13") (pinfunction "13_13") (pintype "passive"))
      (node (ref "J8") (pin "10") (pinfunction "10_10") (pintype "passive"))
      (node (ref "J8") (pin "11") (pinfunction "11_11") (pintype "passive"))
      (node (ref "J8") (pin "12") (pinfunction "12_12") (pintype "passive"))
      (node (ref "J8") (pin "13") (pinfunction "13_13") (pintype "passive"))
      (node (ref "J9") (pin "17") (pinfunction "17_17") (pintype "passive"))
      (node (ref "J9") (pin "18") (pinfunction "18_18") (pintype "passive"))
      (node (ref "J9") (pin "19") (pinfunction "19_19") (pintype "passive"))
      (node (ref "J9") (pin "20") (pinfunction "20_20") (pintype "passive"))
      (node (ref "L1") (pin "1") (pinfunction "1_1") (pintype "passive"))
      (node (ref "U1") (pin "14") (pinfunction "GND_14") (pintype "passive"))
      (node (ref "U1") (pin "27") (pinfunction "GND_27") (pintype "passive"))
      (node (ref "U1") (pin "31") (pinfunction "GND_31") (pintype "passive"))
      (node (ref "U1") (pin "40") (pinfunction "GND_40") (pintype "passive"))
      (node (ref "U1") (pin "42") (pinfunction "GND_42") (pintype "passive"))
      (node (ref "U1") (pin "44") (pinfunction "GND_44") (pintype "passive"))
      (node (ref "U1") (pin "45") (pinfunction "GND_45") (pintype "passive"))
      (node (ref "U1") (pin "48") (pinfunction "GND_48") (pintype "passive"))
      (node (ref "U1") (pin "49") (pinfunction "GND_49") (pintype "passive"))
      (node (ref "U2") (pin "20") (pinfunction "VSS_20") (pintype "passive"))
      (node (ref "U4") (pin "2") (pinfunction "VSS_2") (pintype "passive"))
      (node (ref "U5") (pin "2") (pinfunction "GND_2") (pintype "passive"))
    )
    (net (code "64") (name "unconnected-(A2-Pad3)") (class "Default")
      (node (ref "A2") (pin "3") (pinfunction "3_3") (pintype "passive"))
    )
    (net (code "65") (name "unconnected-(J8-Pad4)") (class "Default")
      (node (ref "J8") (pin "4") (pinfunction "4_4") (pintype "passive"))
    )
    (net (code "66") (name "unconnected-(J8-Pad8)") (class "Default")
      (node (ref "J8") (pin "8") (pinfunction "8_8") (pintype "passive"))
    )
    (net (code "67") (name "unconnected-(J10-Pad4)") (class "Default")
      (node (ref "J10") (pin "4") (pinfunction "4_4") (pintype "passive"))
    )
    (net (code "68") (name "unconnected-(J10-Pad8)") (class "Default")
      (node (ref "J10") (pin "8") (pinfunction "8_8") (pintype "passive"))
    )
    (net (code "69") (name "unconnected-(U2-RA5-Pad2)") (class "Default")
      (node (ref "U2") (pin "2") (pinfunction "RA5_2") (pintype "passive"))
    )
    (net (code "70") (name "unconnected-(U2-RB4-Pad13)") (class "Default")
      (node (ref "U2") (pin "13") (pinfunction "RB4_13") (pintype "passive"))
    )
    (net (code "71") (name "unconnected-(U2-RB6-Pad11)") (class "Default")
      (node (ref "U2") (pin "11") (pinfunction "RB6_11") (pintype "passive"))
    )
    (net (code "72") (name "unconnected-(U2-RC2-Pad14)") (class "Default")
      (node (ref "U2") (pin "14") (pinfunction "RC2_14") (pintype "passive"))
    )
    (net (code "73") (name "unconnected-(U2-RC4-Pad6)") (class "Default")
      (node (ref "U2") (pin "6") (pinfunction "RC4_6") (pintype "passive"))
    )
    (net (code "74") (name "unconnected-(U2-RC5-Pad5)") (class "Default")
      (node (ref "U2") (pin "5") (pinfunction "RC5_5") (pintype "passive"))
    )
    (net (code "75") (name "unconnected-(U2-RC6-Pad8)") (class "Default")
      (node (ref "U2") (pin "8") (pinfunction "RC6_8") (pintype "passive"))
    )
    (net (code "76") (name "unconnected-(U2-RC7-Pad9)") (class "Default")
      (node (ref "U2") (pin "9") (pinfunction "RC7_9") (pintype "passive"))
    )
  )
)
